# p0-001.net
KiCad netlist of a schematic drawn in EAGLE
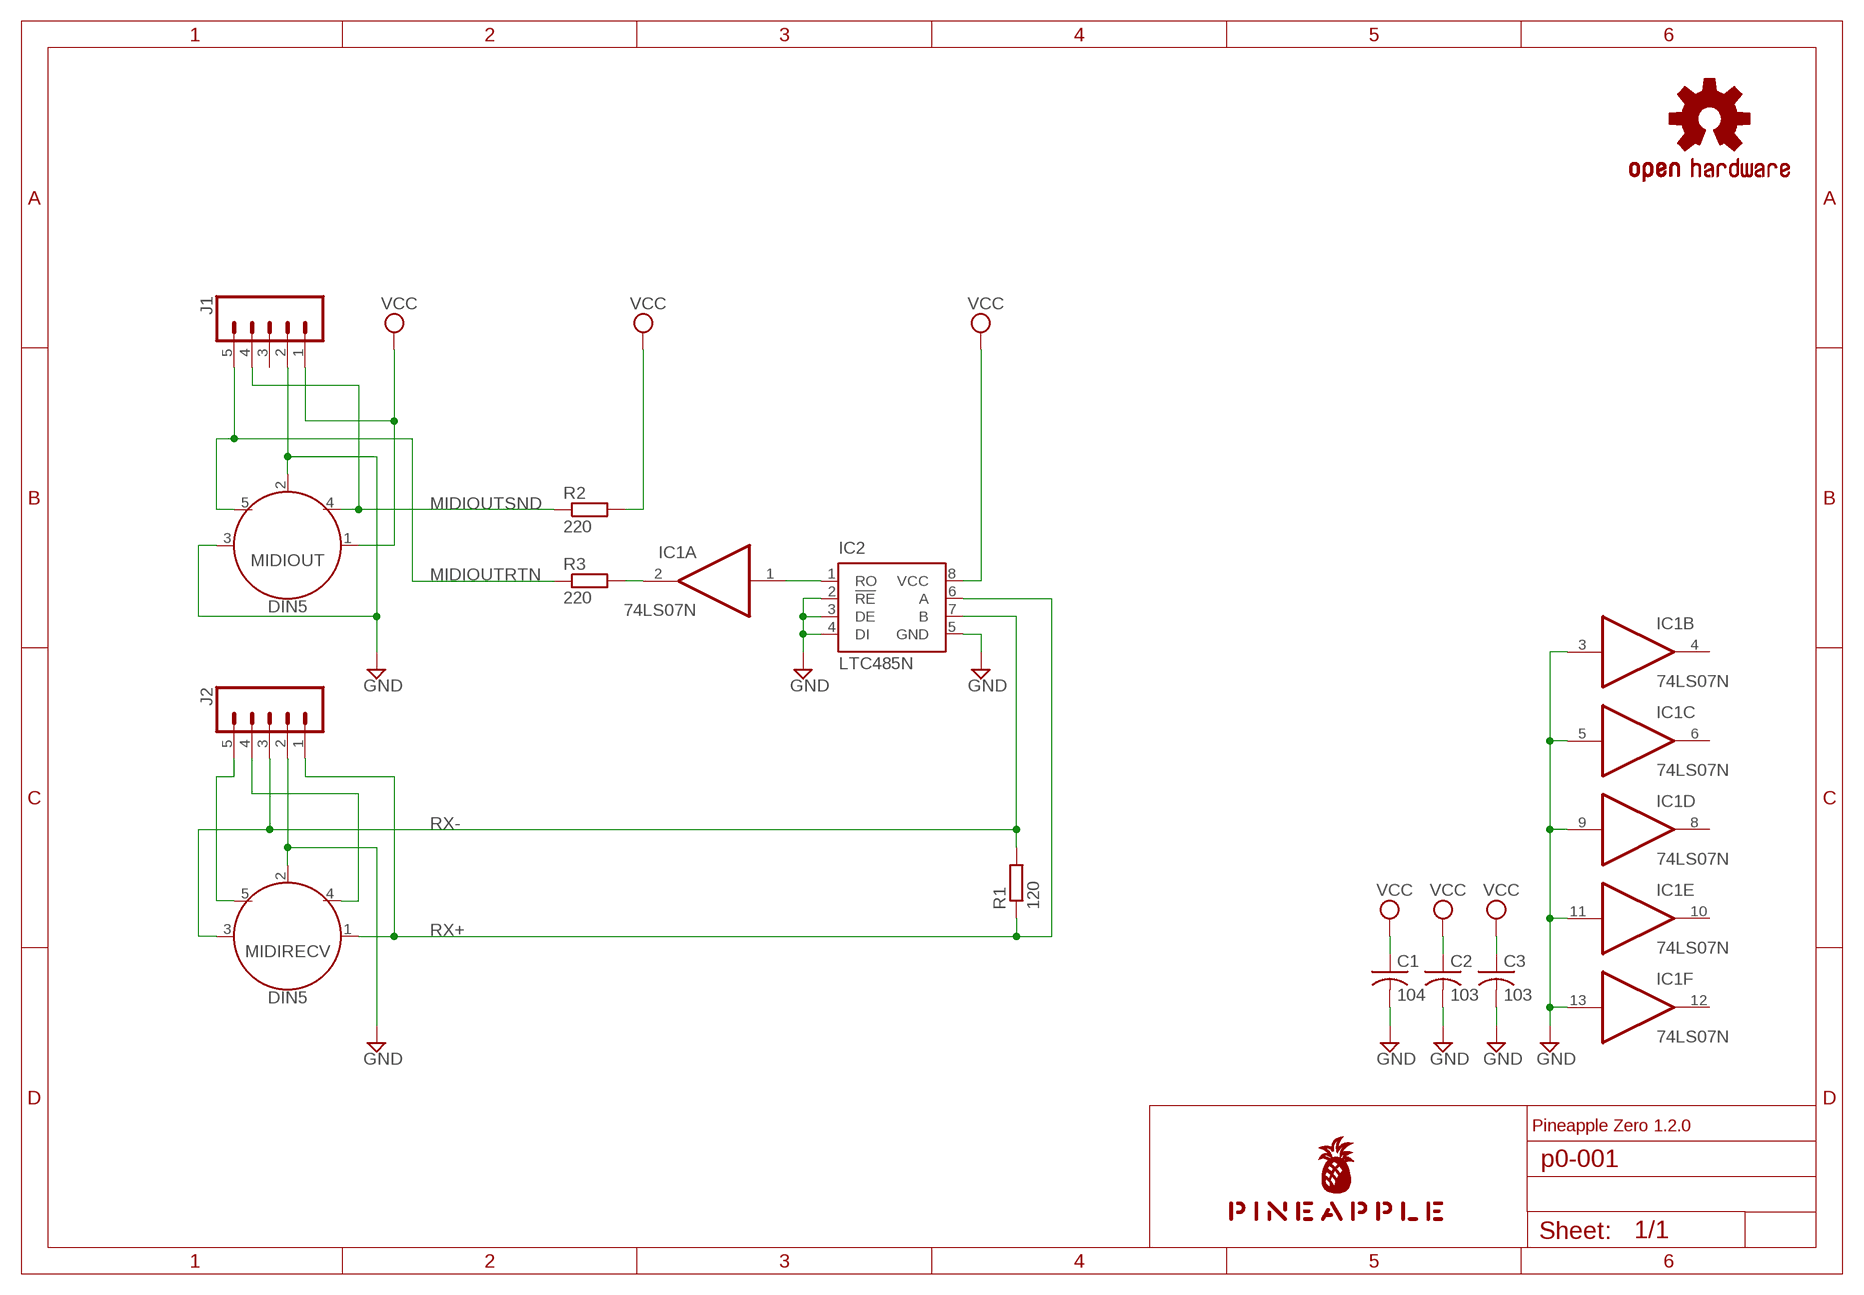
[diagram p0: schematic, sheet 1]

(export (version "E")
  (design (tool "Eeschema 10.0.6"))
  (components
    (comp (ref "C1")
      (value "104")
      (footprint "eagle-import:C025-025X050")
      (libsource (lib "eagle-import") (part "C-US025-025X050"))
    )
    (comp (ref "C2")
      (value "103")
      (footprint "eagle-import:C025-025X050")
      (libsource (lib "eagle-import") (part "C-US025-025X050"))
    )
    (comp (ref "C3")
      (value "103")
      (footprint "eagle-import:C025-025X050")
      (libsource (lib "eagle-import") (part "C-US025-025X050"))
    )
    (comp (ref "IC1")
      (value "74LS07N")
      (footprint "eagle-import:DIL14")
      (libsource (lib "eagle-import") (part "7407NLS"))
    )
    (comp (ref "IC2")
      (value "LTC485N")
      (footprint "eagle-import:DIL08")
      (libsource (lib "eagle-import") (part "LTC485N"))
    )
    (comp (ref "J1")
      (value "CONN_05JST")
      (footprint "eagle-import:JST-5-PTH")
      (libsource (lib "eagle-import") (part "CONN_05JST"))
    )
    (comp (ref "J2")
      (value "CONN_05JST")
      (footprint "eagle-import:JST-5-PTH")
      (libsource (lib "eagle-import") (part "CONN_05JST"))
    )
    (comp (ref "LOGO1")
      (value "OSHW-LOGOS-COPPER")
      (footprint "eagle-import:OSHW-LOGO-S_COPPER")
      (libsource (lib "eagle-import") (part "OSHW-LOGOS-COPPER"))
    )
    (comp (ref "MIDIOUT")
      (value "DIN5")
      (footprint "eagle-import:DIN5-RA-PTH")
      (libsource (lib "eagle-import") (part "DIN5"))
    )
    (comp (ref "MIDIRECV")
      (value "DIN5")
      (footprint "eagle-import:DIN5-RA-PTH")
      (libsource (lib "eagle-import") (part "DIN5"))
    )
    (comp (ref "R1")
      (value "120")
      (footprint "eagle-import:0204_5")
      (libsource (lib "eagle-import") (part "R-EU_0204/5"))
    )
    (comp (ref "R2")
      (value "220")
      (footprint "eagle-import:0204_5")
      (libsource (lib "eagle-import") (part "R-EU_0204/5"))
    )
    (comp (ref "R3")
      (value "220")
      (footprint "eagle-import:0204_5")
      (libsource (lib "eagle-import") (part "R-EU_0204/5"))
    )
    (comp (ref "U$1")
      (value "PINEAPPLE450")
      (footprint "eagle-import:PINEAPPLE450")
      (libsource (lib "eagle-import") (part "PINEAPPLE450"))
    )
  )
  (nets
    (net (code "1") (name "/MIDIOUTRTN") (class "Default")
      (node (ref "J1") (pin "5") (pinfunction "5_5") (pintype "passive"))
      (node (ref "MIDIOUT") (pin "5") (pinfunction "5_5") (pintype "bidirectional"))
      (node (ref "R3") (pin "1") (pinfunction "1_1") (pintype "passive"))
    )
    (net (code "2") (name "/MIDIOUTSND") (class "Default")
      (node (ref "J1") (pin "4") (pinfunction "4_4") (pintype "passive"))
      (node (ref "MIDIOUT") (pin "4") (pinfunction "4_4") (pintype "bidirectional"))
      (node (ref "R2") (pin "1") (pinfunction "1_1") (pintype "passive"))
    )
    (net (code "3") (name "/RX+") (class "Default")
      (node (ref "IC2") (pin "6") (pinfunction "A_6") (pintype "bidirectional"))
      (node (ref "J2") (pin "1") (pinfunction "1_1") (pintype "passive"))
      (node (ref "MIDIRECV") (pin "1") (pinfunction "1_1") (pintype "bidirectional"))
      (node (ref "R1") (pin "1") (pinfunction "1_1") (pintype "passive"))
    )
    (net (code "4") (name "/RX-") (class "Default")
      (node (ref "IC2") (pin "7") (pinfunction "B_7") (pintype "bidirectional"))
      (node (ref "J2") (pin "3") (pinfunction "3_3") (pintype "passive"))
      (node (ref "MIDIRECV") (pin "3") (pinfunction "3_3") (pintype "bidirectional"))
      (node (ref "R1") (pin "2") (pinfunction "2_2") (pintype "passive"))
    )
    (net (code "5") (name "GND") (class "Default")
      (node (ref "C1") (pin "2") (pinfunction "2_2") (pintype "passive"))
      (node (ref "C2") (pin "2") (pinfunction "2_2") (pintype "passive"))
      (node (ref "C3") (pin "2") (pinfunction "2_2") (pintype "passive"))
      (node (ref "IC1") (pin "11") (pinfunction "I_11") (pintype "input"))
      (node (ref "IC1") (pin "13") (pinfunction "I_13") (pintype "input"))
      (node (ref "IC1") (pin "3") (pinfunction "I_3") (pintype "input"))
      (node (ref "IC1") (pin "5") (pinfunction "I_5") (pintype "input"))
      (node (ref "IC1") (pin "9") (pinfunction "I_9") (pintype "input"))
      (node (ref "IC2") (pin "2") (pinfunction "~{RE}_2") (pintype "input"))
      (node (ref "IC2") (pin "3") (pinfunction "DE_3") (pintype "input"))
      (node (ref "IC2") (pin "4") (pinfunction "DI_4") (pintype "input"))
      (node (ref "IC2") (pin "5") (pinfunction "GND_5") (pintype "input"))
      (node (ref "J1") (pin "2") (pinfunction "2_2") (pintype "passive"))
      (node (ref "J2") (pin "2") (pinfunction "2_2") (pintype "passive"))
      (node (ref "MIDIOUT") (pin "2") (pinfunction "2_2") (pintype "bidirectional"))
      (node (ref "MIDIOUT") (pin "3") (pinfunction "3_3") (pintype "bidirectional"))
      (node (ref "MIDIRECV") (pin "2") (pinfunction "2_2") (pintype "bidirectional"))
    )
    (net (code "6") (name "Net-(IC1A-I)") (class "Default")
      (node (ref "IC1") (pin "1") (pinfunction "I_1") (pintype "input"))
      (node (ref "IC2") (pin "1") (pinfunction "RO_1") (pintype "output"))
    )
    (net (code "7") (name "Net-(IC1A-O)") (class "Default")
      (node (ref "IC1") (pin "2") (pinfunction "O_2") (pintype "open_collector"))
      (node (ref "R3") (pin "2") (pinfunction "2_2") (pintype "passive"))
    )
    (net (code "8") (name "Net-(J2-Pad4)") (class "Default")
      (node (ref "J2") (pin "4") (pinfunction "4_4") (pintype "passive"))
      (node (ref "MIDIRECV") (pin "4") (pinfunction "4_4") (pintype "bidirectional"))
    )
    (net (code "9") (name "Net-(J2-Pad5)") (class "Default")
      (node (ref "J2") (pin "5") (pinfunction "5_5") (pintype "passive"))
      (node (ref "MIDIRECV") (pin "5") (pinfunction "5_5") (pintype "bidirectional"))
    )
    (net (code "10") (name "VCC") (class "Default")
      (node (ref "C1") (pin "1") (pinfunction "1_1") (pintype "passive"))
      (node (ref "C2") (pin "1") (pinfunction "1_1") (pintype "passive"))
      (node (ref "C3") (pin "1") (pinfunction "1_1") (pintype "passive"))
      (node (ref "IC2") (pin "8") (pinfunction "VCC_8") (pintype "input"))
      (node (ref "J1") (pin "1") (pinfunction "1_1") (pintype "passive"))
      (node (ref "MIDIOUT") (pin "1") (pinfunction "1_1") (pintype "bidirectional"))
      (node (ref "R2") (pin "2") (pinfunction "2_2") (pintype "passive"))
    )
    (net (code "11") (name "unconnected-(IC1B-O-Pad4)") (class "Default")
      (node (ref "IC1") (pin "4") (pinfunction "O_4") (pintype "open_collector"))
    )
    (net (code "12") (name "unconnected-(IC1C-O-Pad6)") (class "Default")
      (node (ref "IC1") (pin "6") (pinfunction "O_6") (pintype "open_collector"))
    )
    (net (code "13") (name "unconnected-(IC1D-O-Pad8)") (class "Default")
      (node (ref "IC1") (pin "8") (pinfunction "O_8") (pintype "open_collector"))
    )
    (net (code "14") (name "unconnected-(IC1E-O-Pad10)") (class "Default")
      (node (ref "IC1") (pin "10") (pinfunction "O_10") (pintype "open_collector"))
    )
    (net (code "15") (name "unconnected-(IC1F-O-Pad12)") (class "Default")
      (node (ref "IC1") (pin "12") (pinfunction "O_12") (pintype "open_collector"))
    )
    (net (code "16") (name "unconnected-(J1-Pad3)") (class "Default")
      (node (ref "J1") (pin "3") (pinfunction "3_3") (pintype "passive"))
    )
  )
)
